# jevois_com.net
KiCad netlist of a schematic drawn in EAGLE
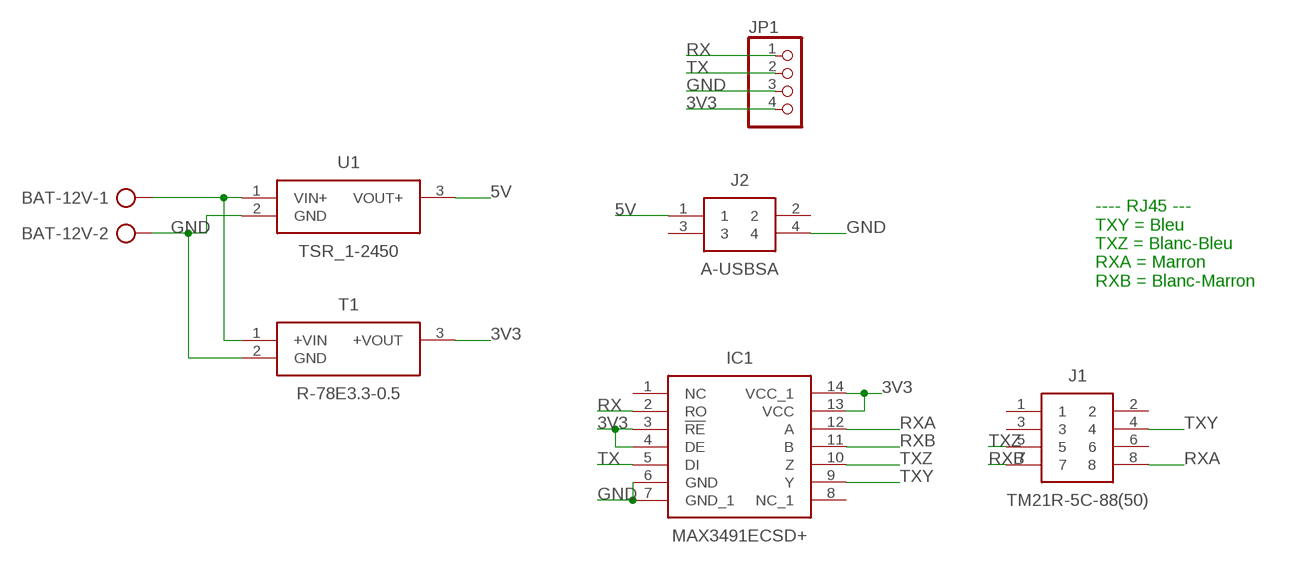
[diagram p0: schematic, sheet 1]

(export (version "E")
  (design (tool "Eeschema 10.0.6"))
  (components
    (comp (ref "BAT-12V")
      (value "AK500/2-H")
      (footprint "eagle-import:AK500_2-H")
      (libsource (lib "eagle-import") (part "AK500/2-H"))
    )
    (comp (ref "IC1")
      (value "MAX3491ECSD+")
      (footprint "eagle-import:SOIC127P600X175-14N")
      (fields (field (name "RS_PART_NUMBER") "7329496"))
      (libsource (lib "eagle-import") (part "MAX3491ECSD+"))
    )
    (comp (ref "J1")
      (value "TM21R-5C-88(50)")
      (footprint "eagle-import:TM21R-5C-88(50)")
      (fields (field (name "RS_PART_NUMBER") "6256710"))
      (libsource (lib "eagle-import") (part "TM21R-5C-88(50)"))
    )
    (comp (ref "J2")
      (value "A-USBSA")
      (footprint "eagle-import:A-USBSA")
      (fields (field (name "RS_PART_NUMBER") "6741325P"))
      (libsource (lib "eagle-import") (part "A-USBSA"))
    )
    (comp (ref "JP1")
      (value "PINHD-1X4")
      (footprint "eagle-import:1X04")
      (libsource (lib "eagle-import") (part "PINHD-1X4"))
    )
    (comp (ref "T1")
      (value "R-78E3.3-0.5")
      (footprint "eagle-import:SHDRV3W100P0_254_1X3_1160X850X")
      (fields (field (name "RS_PART_NUMBER") "7773291"))
      (libsource (lib "eagle-import") (part "R-78E3.3-0.5"))
    )
    (comp (ref "U1")
      (value "TSR_1-2450")
      (footprint "eagle-import:TSR-1-24120")
      (fields
        (field (name "MANUFACTURER_PART_NUMBER") "TSR 1-2450")
        (field (name "RS_PART_NUMBER") "6664379P")
      )
      (libsource (lib "eagle-import") (part "TSR_1-2450"))
    )
  )
  (nets
    (net (code "1") (name "/3V3") (class "Default")
      (node (ref "IC1") (pin "13") (pinfunction "VCC_13") (pintype "power_in"))
      (node (ref "IC1") (pin "14") (pinfunction "VCC_1_14") (pintype "power_in"))
      (node (ref "IC1") (pin "3") (pinfunction "~{RE}_3") (pintype "input"))
      (node (ref "IC1") (pin "4") (pinfunction "DE_4") (pintype "input"))
      (node (ref "JP1") (pin "4") (pinfunction "4_4") (pintype "passive"))
      (node (ref "T1") (pin "3") (pinfunction "+VOUT_3") (pintype "output"))
    )
    (net (code "2") (name "/5V") (class "Default")
      (node (ref "J2") (pin "1") (pinfunction "1_1") (pintype "passive"))
      (node (ref "U1") (pin "3") (pinfunction "VOUT+_3") (pintype "input"))
    )
    (net (code "3") (name "/GND") (class "Default")
      (node (ref "BAT-12V") (pin "2") (pinfunction "KL_2") (pintype "passive"))
      (node (ref "IC1") (pin "6") (pinfunction "GND_6") (pintype "power_in"))
      (node (ref "IC1") (pin "7") (pinfunction "GND_1_7") (pintype "power_in"))
      (node (ref "J2") (pin "4") (pinfunction "4_4") (pintype "passive"))
      (node (ref "JP1") (pin "3") (pinfunction "3_3") (pintype "passive"))
      (node (ref "T1") (pin "2") (pinfunction "GND_2") (pintype "power_in"))
      (node (ref "U1") (pin "2") (pinfunction "GND_2") (pintype "power_in"))
    )
    (net (code "4") (name "/RX") (class "Default")
      (node (ref "IC1") (pin "2") (pinfunction "RO_2") (pintype "output"))
      (node (ref "JP1") (pin "1") (pinfunction "1_1") (pintype "passive"))
    )
    (net (code "5") (name "/RXA") (class "Default")
      (node (ref "IC1") (pin "12") (pinfunction "A_12") (pintype "input"))
      (node (ref "J1") (pin "8") (pinfunction "8_8") (pintype "passive"))
    )
    (net (code "6") (name "/RXB") (class "Default")
      (node (ref "IC1") (pin "11") (pinfunction "B_11") (pintype "input"))
      (node (ref "J1") (pin "7") (pinfunction "7_7") (pintype "passive"))
    )
    (net (code "7") (name "/TX") (class "Default")
      (node (ref "IC1") (pin "5") (pinfunction "DI_5") (pintype "input"))
      (node (ref "JP1") (pin "2") (pinfunction "2_2") (pintype "passive"))
    )
    (net (code "8") (name "/TXY") (class "Default")
      (node (ref "IC1") (pin "9") (pinfunction "Y_9") (pintype "output"))
      (node (ref "J1") (pin "4") (pinfunction "4_4") (pintype "passive"))
    )
    (net (code "9") (name "/TXZ") (class "Default")
      (node (ref "IC1") (pin "10") (pinfunction "Z_10") (pintype "output"))
      (node (ref "J1") (pin "5") (pinfunction "5_5") (pintype "passive"))
    )
    (net (code "10") (name "Net-(BAT-12VA-KL)") (class "Default")
      (node (ref "BAT-12V") (pin "1") (pinfunction "KL_1") (pintype "passive"))
      (node (ref "T1") (pin "1") (pinfunction "+VIN_1") (pintype "input"))
      (node (ref "U1") (pin "1") (pinfunction "VIN+_1") (pintype "input"))
    )
    (net (code "11") (name "unconnected-(IC1-NC-Pad1)") (class "Default")
      (node (ref "IC1") (pin "1") (pinfunction "NC_1") (pintype "no_connect"))
    )
    (net (code "12") (name "unconnected-(IC1-NC_1-Pad8)") (class "Default")
      (node (ref "IC1") (pin "8") (pinfunction "NC_1_8") (pintype "passive"))
    )
    (net (code "13") (name "unconnected-(J1-Pad1)") (class "Default")
      (node (ref "J1") (pin "1") (pinfunction "1_1") (pintype "passive"))
    )
    (net (code "14") (name "unconnected-(J1-Pad2)") (class "Default")
      (node (ref "J1") (pin "2") (pinfunction "2_2") (pintype "passive"))
    )
    (net (code "15") (name "unconnected-(J1-Pad3)") (class "Default")
      (node (ref "J1") (pin "3") (pinfunction "3_3") (pintype "passive"))
    )
    (net (code "16") (name "unconnected-(J1-Pad6)") (class "Default")
      (node (ref "J1") (pin "6") (pinfunction "6_6") (pintype "passive"))
    )
    (net (code "17") (name "unconnected-(J2-Pad2)") (class "Default")
      (node (ref "J2") (pin "2") (pinfunction "2_2") (pintype "passive"))
    )
    (net (code "18") (name "unconnected-(J2-Pad3)") (class "Default")
      (node (ref "J2") (pin "3") (pinfunction "3_3") (pintype "passive"))
    )
  )
)
